# auxDaqUnitTopAnalog2022.net
KiCad netlist of a schematic drawn in EAGLE
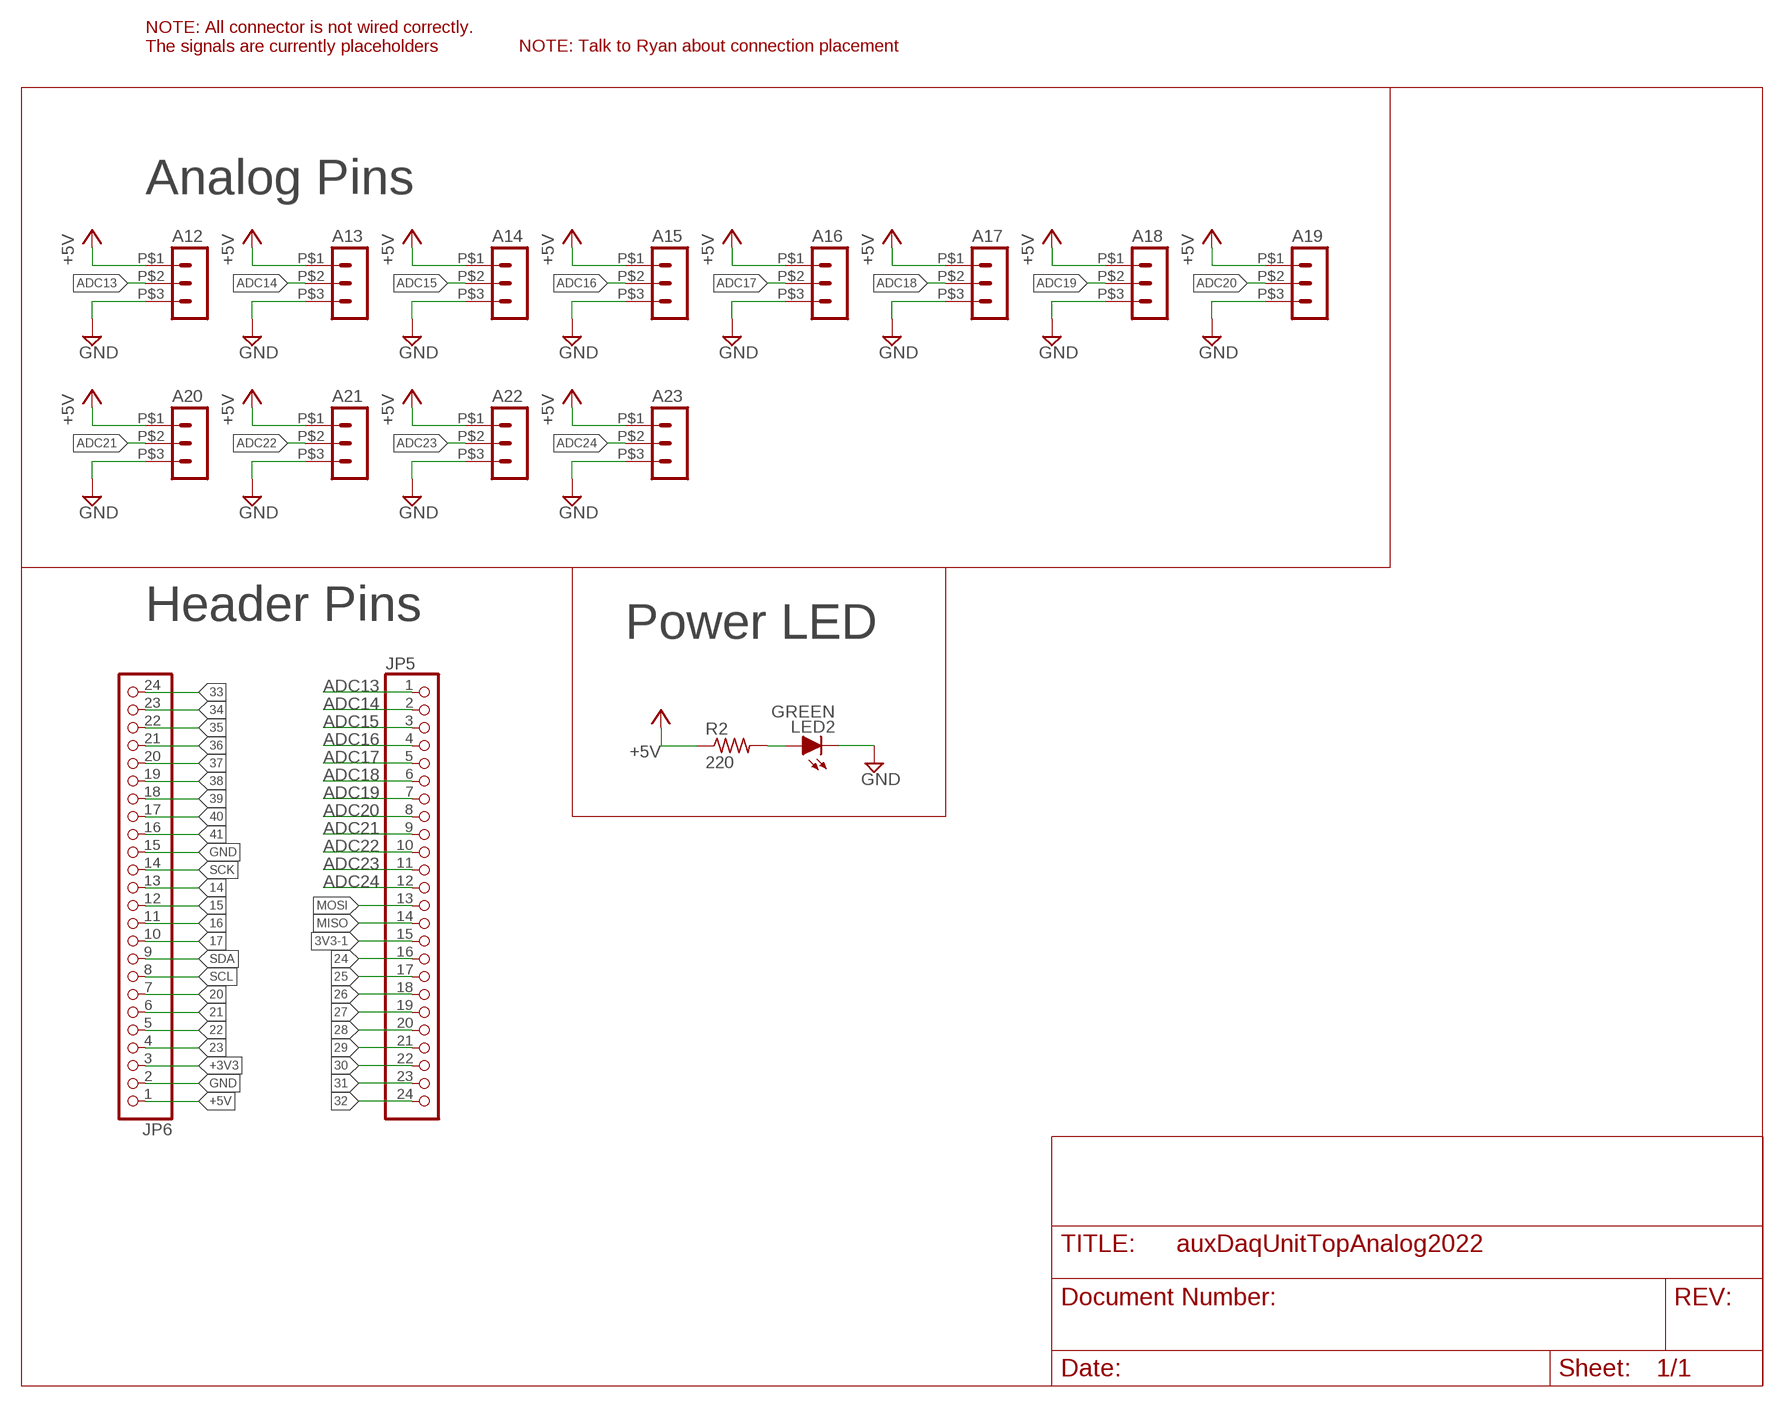
[diagram p0: schematic, sheet 1]

(export (version "E")
  (design (tool "Eeschema 10.0.6"))
  (components
    (comp (ref "A12")
      (value "HEADER_POS3_43650-0300")
      (footprint "eagle-import:43650-0300")
      (libsource (lib "eagle-import") (part "HEADER_POS3_?43650-0300"))
    )
    (comp (ref "A13")
      (value "HEADER_POS3_43650-0300")
      (footprint "eagle-import:43650-0300")
      (libsource (lib "eagle-import") (part "HEADER_POS3_?43650-0300"))
    )
    (comp (ref "A14")
      (value "HEADER_POS3_43650-0300")
      (footprint "eagle-import:43650-0300")
      (libsource (lib "eagle-import") (part "HEADER_POS3_?43650-0300"))
    )
    (comp (ref "A15")
      (value "HEADER_POS3_43650-0300")
      (footprint "eagle-import:43650-0300")
      (libsource (lib "eagle-import") (part "HEADER_POS3_?43650-0300"))
    )
    (comp (ref "A16")
      (value "HEADER_POS3_43650-0300")
      (footprint "eagle-import:43650-0300")
      (libsource (lib "eagle-import") (part "HEADER_POS3_?43650-0300"))
    )
    (comp (ref "A17")
      (value "HEADER_POS3_43650-0300")
      (footprint "eagle-import:43650-0300")
      (libsource (lib "eagle-import") (part "HEADER_POS3_?43650-0300"))
    )
    (comp (ref "A18")
      (value "HEADER_POS3_43650-0300")
      (footprint "eagle-import:43650-0300")
      (libsource (lib "eagle-import") (part "HEADER_POS3_?43650-0300"))
    )
    (comp (ref "A19")
      (value "HEADER_POS3_43650-0300")
      (footprint "eagle-import:43650-0300")
      (libsource (lib "eagle-import") (part "HEADER_POS3_?43650-0300"))
    )
    (comp (ref "A20")
      (value "HEADER_POS3_43650-0300")
      (footprint "eagle-import:43650-0300")
      (libsource (lib "eagle-import") (part "HEADER_POS3_?43650-0300"))
    )
    (comp (ref "A21")
      (value "HEADER_POS3_43650-0300")
      (footprint "eagle-import:43650-0300")
      (libsource (lib "eagle-import") (part "HEADER_POS3_?43650-0300"))
    )
    (comp (ref "A22")
      (value "HEADER_POS3_43650-0300")
      (footprint "eagle-import:43650-0300")
      (libsource (lib "eagle-import") (part "HEADER_POS3_?43650-0300"))
    )
    (comp (ref "A23")
      (value "HEADER_POS3_43650-0300")
      (footprint "eagle-import:43650-0300")
      (libsource (lib "eagle-import") (part "HEADER_POS3_?43650-0300"))
    )
    (comp (ref "JP5")
      (value "PINHD-1X24")
      (footprint "eagle-import:1X24")
      (libsource (lib "eagle-import") (part "PINHD-1X24"))
    )
    (comp (ref "JP6")
      (value "PINHD-1X24")
      (footprint "eagle-import:1X24")
      (libsource (lib "eagle-import") (part "PINHD-1X24"))
    )
    (comp (ref "LED2")
      (value "GREEN")
      (footprint "eagle-import:LED-603")
      (libsource (lib "eagle-import") (part "LED-0603"))
    )
    (comp (ref "R2")
      (value "220")
      (footprint "eagle-import:R0603")
      (libsource (lib "eagle-import") (part "RES_SMDR0603"))
    )
  )
  (nets
    (net (code "1") (name "+3V3") (class "Default")
      (node (ref "JP6") (pin "3") (pinfunction "3_3") (pintype "passive"))
    )
    (net (code "2") (name "+5V") (class "Default")
      (node (ref "A12") (pin "P$1") (pinfunction "1_P$1") (pintype "passive"))
      (node (ref "A13") (pin "P$1") (pinfunction "1_P$1") (pintype "passive"))
      (node (ref "A14") (pin "P$1") (pinfunction "1_P$1") (pintype "passive"))
      (node (ref "A15") (pin "P$1") (pinfunction "1_P$1") (pintype "passive"))
      (node (ref "A16") (pin "P$1") (pinfunction "1_P$1") (pintype "passive"))
      (node (ref "A17") (pin "P$1") (pinfunction "1_P$1") (pintype "passive"))
      (node (ref "A18") (pin "P$1") (pinfunction "1_P$1") (pintype "passive"))
      (node (ref "A19") (pin "P$1") (pinfunction "1_P$1") (pintype "passive"))
      (node (ref "A20") (pin "P$1") (pinfunction "1_P$1") (pintype "passive"))
      (node (ref "A21") (pin "P$1") (pinfunction "1_P$1") (pintype "passive"))
      (node (ref "A22") (pin "P$1") (pinfunction "1_P$1") (pintype "passive"))
      (node (ref "A23") (pin "P$1") (pinfunction "1_P$1") (pintype "passive"))
      (node (ref "JP6") (pin "1") (pinfunction "1_1") (pintype "passive"))
      (node (ref "R2") (pin "1") (pinfunction "1_1") (pintype "passive"))
    )
    (net (code "3") (name "3V3-1") (class "Default")
      (node (ref "JP5") (pin "15") (pinfunction "15_15") (pintype "passive"))
    )
    (net (code "4") (name "14") (class "Default")
      (node (ref "JP6") (pin "13") (pinfunction "13_13") (pintype "passive"))
    )
    (net (code "5") (name "15") (class "Default")
      (node (ref "JP6") (pin "12") (pinfunction "12_12") (pintype "passive"))
    )
    (net (code "6") (name "16") (class "Default")
      (node (ref "JP6") (pin "11") (pinfunction "11_11") (pintype "passive"))
    )
    (net (code "7") (name "17") (class "Default")
      (node (ref "JP6") (pin "10") (pinfunction "10_10") (pintype "passive"))
    )
    (net (code "8") (name "20") (class "Default")
      (node (ref "JP6") (pin "7") (pinfunction "7_7") (pintype "passive"))
    )
    (net (code "9") (name "21") (class "Default")
      (node (ref "JP6") (pin "6") (pinfunction "6_6") (pintype "passive"))
    )
    (net (code "10") (name "22") (class "Default")
      (node (ref "JP6") (pin "5") (pinfunction "5_5") (pintype "passive"))
    )
    (net (code "11") (name "23") (class "Default")
      (node (ref "JP6") (pin "4") (pinfunction "4_4") (pintype "passive"))
    )
    (net (code "12") (name "24") (class "Default")
      (node (ref "JP5") (pin "16") (pinfunction "16_16") (pintype "passive"))
    )
    (net (code "13") (name "25") (class "Default")
      (node (ref "JP5") (pin "17") (pinfunction "17_17") (pintype "passive"))
    )
    (net (code "14") (name "26") (class "Default")
      (node (ref "JP5") (pin "18") (pinfunction "18_18") (pintype "passive"))
    )
    (net (code "15") (name "27") (class "Default")
      (node (ref "JP5") (pin "19") (pinfunction "19_19") (pintype "passive"))
    )
    (net (code "16") (name "28") (class "Default")
      (node (ref "JP5") (pin "20") (pinfunction "20_20") (pintype "passive"))
    )
    (net (code "17") (name "29") (class "Default")
      (node (ref "JP5") (pin "21") (pinfunction "21_21") (pintype "passive"))
    )
    (net (code "18") (name "30") (class "Default")
      (node (ref "JP5") (pin "22") (pinfunction "22_22") (pintype "passive"))
    )
    (net (code "19") (name "31") (class "Default")
      (node (ref "JP5") (pin "23") (pinfunction "23_23") (pintype "passive"))
    )
    (net (code "20") (name "32") (class "Default")
      (node (ref "JP5") (pin "24") (pinfunction "24_24") (pintype "passive"))
    )
    (net (code "21") (name "33") (class "Default")
      (node (ref "JP6") (pin "24") (pinfunction "24_24") (pintype "passive"))
    )
    (net (code "22") (name "34") (class "Default")
      (node (ref "JP6") (pin "23") (pinfunction "23_23") (pintype "passive"))
    )
    (net (code "23") (name "35") (class "Default")
      (node (ref "JP6") (pin "22") (pinfunction "22_22") (pintype "passive"))
    )
    (net (code "24") (name "36") (class "Default")
      (node (ref "JP6") (pin "21") (pinfunction "21_21") (pintype "passive"))
    )
    (net (code "25") (name "37") (class "Default")
      (node (ref "JP6") (pin "20") (pinfunction "20_20") (pintype "passive"))
    )
    (net (code "26") (name "38") (class "Default")
      (node (ref "JP6") (pin "19") (pinfunction "19_19") (pintype "passive"))
    )
    (net (code "27") (name "39") (class "Default")
      (node (ref "JP6") (pin "18") (pinfunction "18_18") (pintype "passive"))
    )
    (net (code "28") (name "40") (class "Default")
      (node (ref "JP6") (pin "17") (pinfunction "17_17") (pintype "passive"))
    )
    (net (code "29") (name "41") (class "Default")
      (node (ref "JP6") (pin "16") (pinfunction "16_16") (pintype "passive"))
    )
    (net (code "30") (name "ADC13") (class "Default")
      (node (ref "A12") (pin "P$2") (pinfunction "2_P$2") (pintype "passive"))
      (node (ref "JP5") (pin "1") (pinfunction "1_1") (pintype "passive"))
    )
    (net (code "31") (name "ADC14") (class "Default")
      (node (ref "A13") (pin "P$2") (pinfunction "2_P$2") (pintype "passive"))
      (node (ref "JP5") (pin "2") (pinfunction "2_2") (pintype "passive"))
    )
    (net (code "32") (name "ADC15") (class "Default")
      (node (ref "A14") (pin "P$2") (pinfunction "2_P$2") (pintype "passive"))
      (node (ref "JP5") (pin "3") (pinfunction "3_3") (pintype "passive"))
    )
    (net (code "33") (name "ADC16") (class "Default")
      (node (ref "A15") (pin "P$2") (pinfunction "2_P$2") (pintype "passive"))
      (node (ref "JP5") (pin "4") (pinfunction "4_4") (pintype "passive"))
    )
    (net (code "34") (name "ADC17") (class "Default")
      (node (ref "A16") (pin "P$2") (pinfunction "2_P$2") (pintype "passive"))
      (node (ref "JP5") (pin "5") (pinfunction "5_5") (pintype "passive"))
    )
    (net (code "35") (name "ADC18") (class "Default")
      (node (ref "A17") (pin "P$2") (pinfunction "2_P$2") (pintype "passive"))
      (node (ref "JP5") (pin "6") (pinfunction "6_6") (pintype "passive"))
    )
    (net (code "36") (name "ADC19") (class "Default")
      (node (ref "A18") (pin "P$2") (pinfunction "2_P$2") (pintype "passive"))
      (node (ref "JP5") (pin "7") (pinfunction "7_7") (pintype "passive"))
    )
    (net (code "37") (name "ADC20") (class "Default")
      (node (ref "A19") (pin "P$2") (pinfunction "2_P$2") (pintype "passive"))
      (node (ref "JP5") (pin "8") (pinfunction "8_8") (pintype "passive"))
    )
    (net (code "38") (name "ADC21") (class "Default")
      (node (ref "A20") (pin "P$2") (pinfunction "2_P$2") (pintype "passive"))
      (node (ref "JP5") (pin "9") (pinfunction "9_9") (pintype "passive"))
    )
    (net (code "39") (name "ADC22") (class "Default")
      (node (ref "A21") (pin "P$2") (pinfunction "2_P$2") (pintype "passive"))
      (node (ref "JP5") (pin "10") (pinfunction "10_10") (pintype "passive"))
    )
    (net (code "40") (name "ADC23") (class "Default")
      (node (ref "A22") (pin "P$2") (pinfunction "2_P$2") (pintype "passive"))
      (node (ref "JP5") (pin "11") (pinfunction "11_11") (pintype "passive"))
    )
    (net (code "41") (name "ADC24") (class "Default")
      (node (ref "A23") (pin "P$2") (pinfunction "2_P$2") (pintype "passive"))
      (node (ref "JP5") (pin "12") (pinfunction "12_12") (pintype "passive"))
    )
    (net (code "42") (name "GND") (class "Default")
      (node (ref "A12") (pin "P$3") (pinfunction "3_P$3") (pintype "passive"))
      (node (ref "A13") (pin "P$3") (pinfunction "3_P$3") (pintype "passive"))
      (node (ref "A14") (pin "P$3") (pinfunction "3_P$3") (pintype "passive"))
      (node (ref "A15") (pin "P$3") (pinfunction "3_P$3") (pintype "passive"))
      (node (ref "A16") (pin "P$3") (pinfunction "3_P$3") (pintype "passive"))
      (node (ref "A17") (pin "P$3") (pinfunction "3_P$3") (pintype "passive"))
      (node (ref "A18") (pin "P$3") (pinfunction "3_P$3") (pintype "passive"))
      (node (ref "A19") (pin "P$3") (pinfunction "3_P$3") (pintype "passive"))
      (node (ref "A20") (pin "P$3") (pinfunction "3_P$3") (pintype "passive"))
      (node (ref "A21") (pin "P$3") (pinfunction "3_P$3") (pintype "passive"))
      (node (ref "A22") (pin "P$3") (pinfunction "3_P$3") (pintype "passive"))
      (node (ref "A23") (pin "P$3") (pinfunction "3_P$3") (pintype "passive"))
      (node (ref "JP6") (pin "15") (pinfunction "15_15") (pintype "passive"))
      (node (ref "JP6") (pin "2") (pinfunction "2_2") (pintype "passive"))
      (node (ref "LED2") (pin "C") (pinfunction "C_C") (pintype "passive"))
    )
    (net (code "43") (name "MISO") (class "Default")
      (node (ref "JP5") (pin "14") (pinfunction "14_14") (pintype "passive"))
    )
    (net (code "44") (name "MOSI") (class "Default")
      (node (ref "JP5") (pin "13") (pinfunction "13_13") (pintype "passive"))
    )
    (net (code "45") (name "Net-(LED2-PadA)") (class "Default")
      (node (ref "LED2") (pin "A") (pinfunction "A_A") (pintype "passive"))
      (node (ref "R2") (pin "2") (pinfunction "2_2") (pintype "passive"))
    )
    (net (code "46") (name "SCK") (class "Default")
      (node (ref "JP6") (pin "14") (pinfunction "14_14") (pintype "passive"))
    )
    (net (code "47") (name "SCL") (class "Default")
      (node (ref "JP6") (pin "8") (pinfunction "8_8") (pintype "passive"))
    )
    (net (code "48") (name "SDA") (class "Default")
      (node (ref "JP6") (pin "9") (pinfunction "9_9") (pintype "passive"))
    )
  )
)
